# CAN.net
KiCad netlist of a schematic drawn in Altium Designer
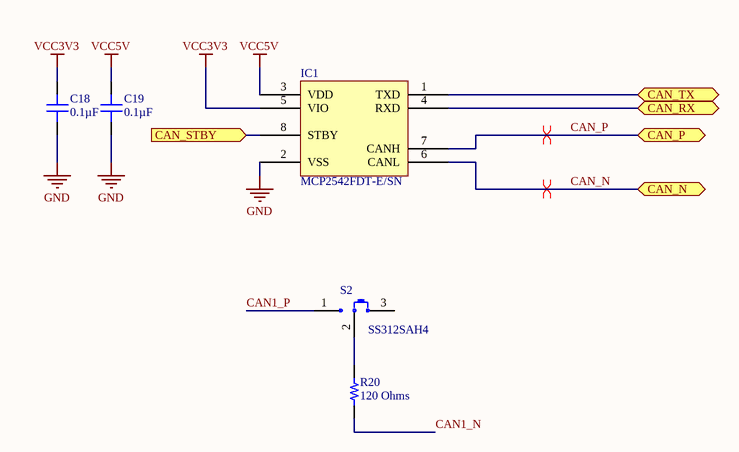
[diagram p0: CAN.SchDoc]

(export (version "E")
  (design (tool "Eeschema 10.0.6"))
  (components
    (comp (ref "C18")
      (value "0.1µF")
      (footprint "CAP 0201_0603")
      (description "CAP CER 0.1UF 16V X5R 0201")
      (fields (field (name "PART NUMBER") "EMK063BJ104KP-F") (field (name "MANUFACTURER") "Taiyo Yuden"))
      (libsource (lib "Celestial") (part "Capacitor"))
    )
    (comp (ref "C19")
      (value "0.1µF")
      (footprint "CAP 0201_0603")
      (description "CAP CER 0.1UF 16V X5R 0201")
      (fields (field (name "PART NUMBER") "EMK063BJ104KP-F") (field (name "MANUFACTURER") "Taiyo Yuden"))
      (libsource (lib "Celestial") (part "Capacitor"))
    )
    (comp (ref "IC1")
      (value "MCP2542FDT-E/SN")
      (footprint "MICROCHIP SOIC-8 150MIL WIDE")
      (description "IC TRANSCEIVER 1/1 8SOIC")
      (fields (field (name "MANUFACTURER") "Microchip Technology"))
      (libsource (lib "Celestial") (part "MICROCHIP MCP2542FD"))
    )
    (comp (ref "R20")
      (value "120 Ohms")
      (footprint "RES 0402_1005")
      (description "RES SMD 120 OHM 5% 1/16W 0402")
      (fields (field (name "PART NUMBER") "RC0402JR-07120RL") (field (name "MANUFACTURER") "Yageo"))
      (libsource (lib "CAL") (part "Resistor"))
    )
    (comp (ref "S2")
      (value "SS312SAH4")
      (footprint "NKK SS312SAH4")
      (description "SWITCH SLIDE SPDT 0.4VA 28V")
      (fields (field (name "MANUFACTURER") "NKK Switches"))
      (libsource (lib "CAL") (part "NKK SS312"))
    )
  )
  (nets
    (net (code "1") (name "/CAN1_N") (class "Default")
      (node (ref "R20") (pin "1") (pinfunction "1_1") (pintype "passive"))
    )
    (net (code "2") (name "/CAN1_P") (class "Default")
      (node (ref "S2") (pin "1") (pinfunction "1_1") (pintype "passive"))
    )
    (net (code "3") (name "/CAN_N") (class "Default")
      (node (ref "IC1") (pin "6") (pinfunction "CANL_6") (pintype "passive"))
    )
    (net (code "4") (name "/CAN_P") (class "Default")
      (node (ref "IC1") (pin "7") (pinfunction "CANH_7") (pintype "passive"))
    )
    (net (code "5") (name "/CAN_RX") (class "Default")
      (node (ref "IC1") (pin "4") (pinfunction "RXD_4") (pintype "passive"))
    )
    (net (code "6") (name "/CAN_STBY") (class "Default")
      (node (ref "IC1") (pin "8") (pinfunction "STBY_8") (pintype "passive"))
    )
    (net (code "7") (name "/CAN_TX") (class "Default")
      (node (ref "IC1") (pin "1") (pinfunction "TXD_1") (pintype "passive"))
    )
    (net (code "8") (name "GND") (class "Default")
      (node (ref "C18") (pin "1") (pinfunction "1_1") (pintype "passive"))
      (node (ref "C19") (pin "1") (pinfunction "1_1") (pintype "passive"))
      (node (ref "IC1") (pin "2") (pinfunction "VSS_2") (pintype "passive"))
    )
    (net (code "9") (name "Net-(S2-COM)") (class "Default")
      (node (ref "R20") (pin "2") (pinfunction "2_2") (pintype "passive"))
      (node (ref "S2") (pin "2") (pinfunction "COM_2") (pintype "passive"))
    )
    (net (code "10") (name "VCC3V3") (class "Default")
      (node (ref "C18") (pin "2") (pinfunction "2_2") (pintype "passive"))
      (node (ref "IC1") (pin "5") (pinfunction "VIO_5") (pintype "passive"))
    )
    (net (code "11") (name "VCC5V") (class "Default")
      (node (ref "C19") (pin "2") (pinfunction "2_2") (pintype "passive"))
      (node (ref "IC1") (pin "3") (pinfunction "VDD_3") (pintype "passive"))
    )
    (net (code "12") (name "unconnected-(S2-Pad3)") (class "Default")
      (node (ref "S2") (pin "3") (pinfunction "3_3") (pintype "passive"))
    )
  )
)
